# Sheet2.net
KiCad netlist of a schematic drawn in Altium Designer
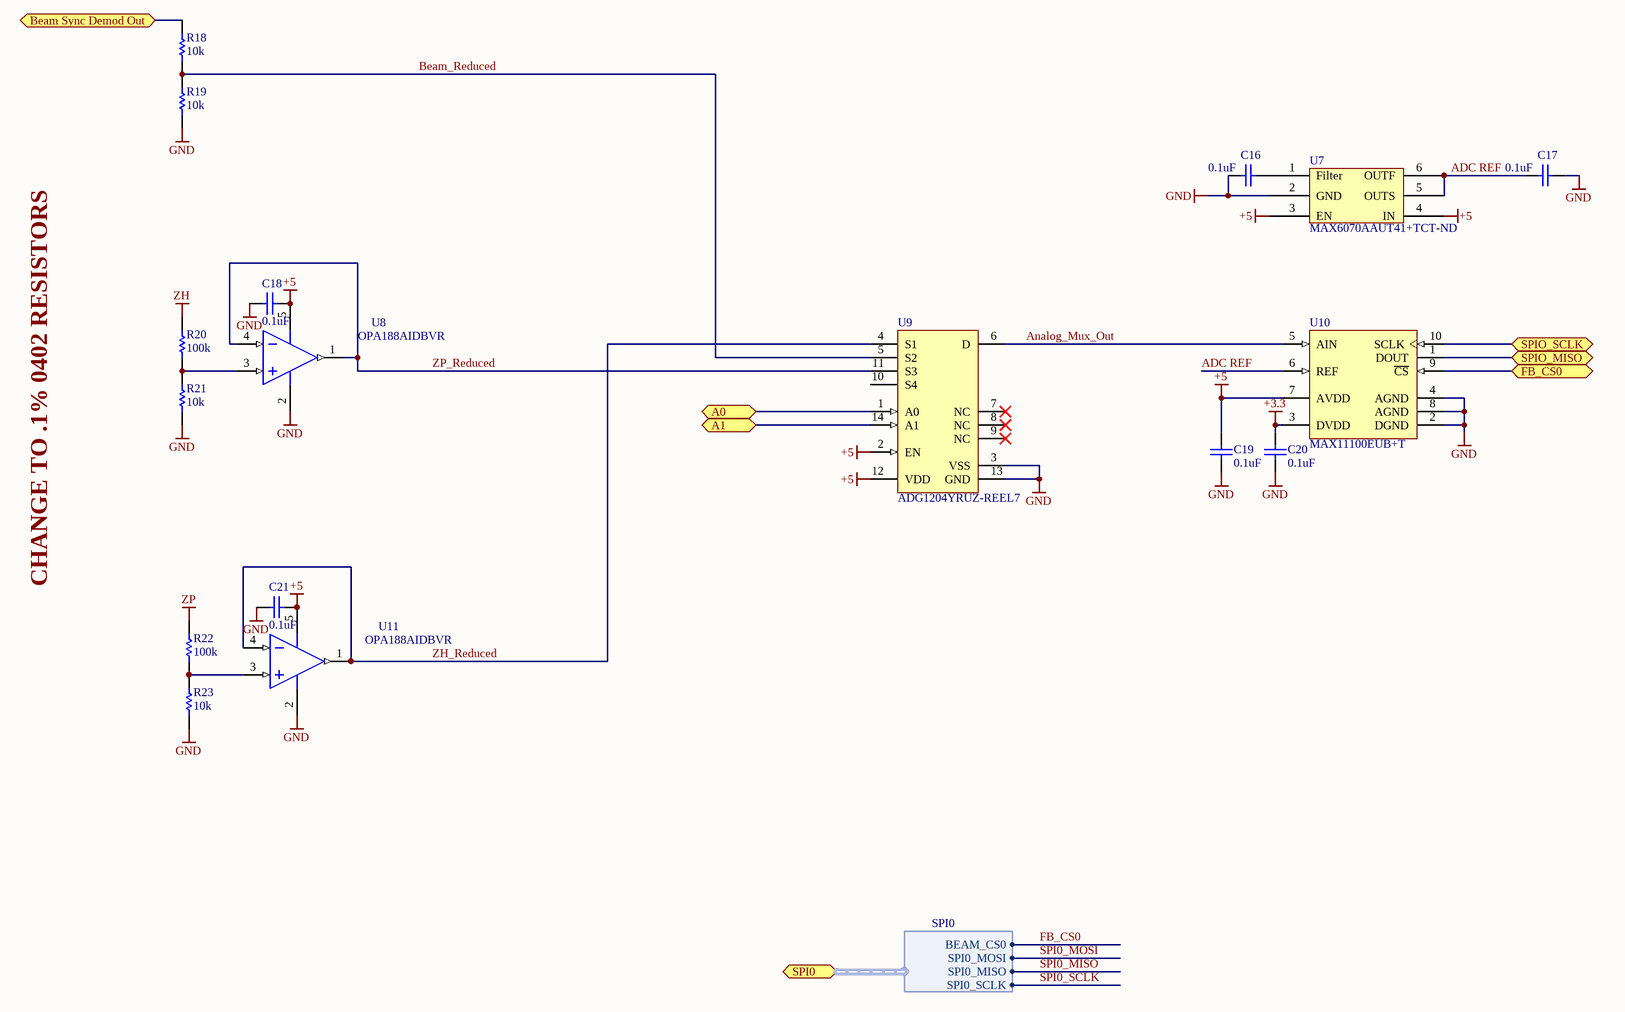
[diagram p0: Sheet2.SchDoc]

(export (version "E")
  (design (tool "Eeschema 10.0.6"))
  (components
    (comp (ref "C16")
      (value "0.1uF")
      (footprint "CAPC0402(1005)60_L")
      (description "CAP CER 0.1UF 10V X7R 0402")
      (fields
        (field (name "MANUFACTURER") "Murata Electronics North America")
        (field (name "MANUFACTURER PART NUMBER") "GRM155R71A104KA01D")
      )
      (libsource (lib "Altium Content Vault") (part "CMP-1034-00252-1"))
    )
    (comp (ref "C17")
      (value "0.1uF")
      (footprint "CAPC0402(1005)60_L")
      (description "CAP CER 0.1UF 10V X7R 0402")
      (fields
        (field (name "MANUFACTURER") "Murata Electronics North America")
        (field (name "MANUFACTURER PART NUMBER") "GRM155R71A104KA01D")
      )
      (libsource (lib "Altium Content Vault") (part "CMP-1034-00252-1"))
    )
    (comp (ref "C18")
      (value "0.1uF")
      (footprint "CAPC0402(1005)60_L")
      (description "CAP CER 0.1UF 10V X7R 0402")
      (fields
        (field (name "MANUFACTURER") "Murata Electronics North America")
        (field (name "MANUFACTURER PART NUMBER") "GRM155R71A104KA01D")
      )
      (libsource (lib "Altium Content Vault") (part "CMP-1034-00252-1"))
    )
    (comp (ref "C19")
      (value "0.1uF")
      (footprint "CAPC0402(1005)60_L")
      (description "CAP CER 0.1UF 10V X7R 0402")
      (fields
        (field (name "MANUFACTURER") "Murata Electronics North America")
        (field (name "MANUFACTURER PART NUMBER") "GRM155R71A104KA01D")
      )
      (libsource (lib "Altium Content Vault") (part "CMP-1034-00252-1"))
    )
    (comp (ref "C20")
      (value "0.1uF")
      (footprint "CAPC0402(1005)60_L")
      (description "CAP CER 0.1UF 10V X7R 0402")
      (fields
        (field (name "MANUFACTURER") "Murata Electronics North America")
        (field (name "MANUFACTURER PART NUMBER") "GRM155R71A104KA01D")
      )
      (libsource (lib "Altium Content Vault") (part "CMP-1034-00252-1"))
    )
    (comp (ref "C21")
      (value "0.1uF")
      (footprint "CAPC0402(1005)60_L")
      (description "CAP CER 0.1UF 10V X7R 0402")
      (fields
        (field (name "MANUFACTURER") "Murata Electronics North America")
        (field (name "MANUFACTURER PART NUMBER") "GRM155R71A104KA01D")
      )
      (libsource (lib "Altium Content Vault") (part "CMP-1034-00252-1"))
    )
    (comp (ref "R18")
      (value "10k")
      (footprint "RESC0402(1005)_M")
      (description "RES SMD 10K OHM 1% 1/8W 0402")
      (fields
        (field (name "MANUFACTURER") "Vishay Dale")
        (field (name "MANUFACTURER PART NUMBER") "CRCW0402100KFKEDHP")
      )
      (libsource (lib "Altium Content Vault") (part "CMP-1011-00651-1"))
    )
    (comp (ref "R19")
      (value "10k")
      (footprint "RESC0402(1005)_M")
      (description "RES SMD 10K OHM 1% 1/8W 0402")
      (fields
        (field (name "MANUFACTURER") "Vishay Dale")
        (field (name "MANUFACTURER PART NUMBER") "CRCW0402100KFKEDHP")
      )
      (libsource (lib "Altium Content Vault") (part "CMP-1011-00651-1"))
    )
    (comp (ref "R20")
      (value "100k")
      (footprint "RESC0402(1005)_M")
      (description "RES SMD 100K OHM 1% 1/8W 0402")
      (fields
        (field (name "MANUFACTURER") "Vishay Dale")
        (field (name "MANUFACTURER PART NUMBER") "CRCW0402100KFKEDHP")
      )
      (libsource (lib "Altium Content Vault") (part "CMP-1011-00651-1"))
    )
    (comp (ref "R21")
      (value "10k")
      (footprint "RESC0402(1005)_M")
      (description "RES SMD 10K OHM 1% 1/8W 0402")
      (fields
        (field (name "MANUFACTURER") "Vishay Dale")
        (field (name "MANUFACTURER PART NUMBER") "CRCW0402100KFKEDHP")
      )
      (libsource (lib "Altium Content Vault") (part "CMP-1011-00651-1"))
    )
    (comp (ref "R22")
      (value "100k")
      (footprint "RESC0402(1005)_M")
      (description "RES SMD 100K OHM 1% 1/8W 0402")
      (fields
        (field (name "MANUFACTURER") "Vishay Dale")
        (field (name "MANUFACTURER PART NUMBER") "CRCW0402100KFKEDHP")
      )
      (libsource (lib "Altium Content Vault") (part "CMP-1011-00651-1"))
    )
    (comp (ref "R23")
      (value "10k")
      (footprint "RESC0402(1005)_M")
      (description "RES SMD 10K OHM 1% 1/8W 0402")
      (fields
        (field (name "MANUFACTURER") "Vishay Dale")
        (field (name "MANUFACTURER PART NUMBER") "CRCW0402100KFKEDHP")
      )
      (libsource (lib "Altium Content Vault") (part "CMP-1011-00651-1"))
    )
    (comp (ref "U7")
      (value "MAX6070AAUT41+T")
      (footprint "SOT95P280X445-6N")
      (description "IC VREF SERIES 4.096V SOT23")
      (fields
        (field (name "SUPPLIER PART NUMBER 1") "MAX6070AAUT41+TCT-ND")
        (field (name "MANUFACTURER") "Maxim Integrated")
        (field (name "TOLERANCE") "±0.04%")
      )
      (libsource (lib "ZLS_Schematic_lib") (part "MAX6070AAUT41+T"))
    )
    (comp (ref "U8")
      (value "OPA188AIDBVR")
      (footprint "DBV0005A_M")
      (fields (field (name "MANUFACTURER") "Texas Instruments"))
      (libsource (lib "Altium Content Vault") (part "CMP-0809-00005-2"))
    )
    (comp (ref "U9")
      (value "ADG1204YRUZ-REEL7")
      (footprint "ADI-RU-14_L")
      (fields (field (name "MANUFACTURER") "Analog Devices"))
      (libsource (lib "Altium Content Vault") (part "ADI-ADG1204-RU-14"))
    )
    (comp (ref "U10")
      (value "MAX11100EUB+T")
      (footprint "U10+2_L")
      (description "16-Bit, +5V, 200ksps ADC with 10uA Shutdown, 10-Pin uMAX, -40°C to +85°C, Pb-Free, Tape and Reel")
      (libsource (lib "Altium Content Vault") (part "CON-ADC-MAX11100-IL10"))
    )
    (comp (ref "U11")
      (value "OPA188AIDBVR")
      (footprint "DBV0005A_M")
      (fields (field (name "MANUFACTURER") "Texas Instruments"))
      (libsource (lib "Altium Content Vault") (part "CMP-0809-00005-2"))
    )
  )
  (nets
    (net (code "2") (name "+3.3") (class "Default")
      (node (ref "C20") (pin "1") (pinfunction "1_1") (pintype "passive"))
      (node (ref "U10") (pin "3") (pinfunction "DVDD_3") (pintype "power_in"))
    )
    (net (code "3") (name "+5") (class "Default")
      (node (ref "C18") (pin "2") (pinfunction "2_2") (pintype "passive"))
      (node (ref "C19") (pin "1") (pinfunction "1_1") (pintype "passive"))
      (node (ref "C21") (pin "2") (pinfunction "2_2") (pintype "passive"))
      (node (ref "U10") (pin "7") (pinfunction "AVDD_7") (pintype "power_in"))
      (node (ref "U11") (pin "5") (pinfunction "V+_5") (pintype "power_in"))
      (node (ref "U7") (pin "3") (pinfunction "EN_3") (pintype "passive"))
      (node (ref "U7") (pin "4") (pinfunction "IN_4") (pintype "passive"))
      (node (ref "U8") (pin "5") (pinfunction "V+_5") (pintype "power_in"))
      (node (ref "U9") (pin "12") (pinfunction "VDD_12") (pintype "power_in"))
      (node (ref "U9") (pin "2") (pinfunction "EN_2") (pintype "input"))
    )
    (net (code "4") (name "/A0") (class "Default")
      (node (ref "U9") (pin "1") (pinfunction "A0_1") (pintype "input"))
    )
    (net (code "5") (name "/A1") (class "Default")
      (node (ref "U9") (pin "14") (pinfunction "A1_14") (pintype "input"))
    )
    (net (code "6") (name "/ADC REF") (class "Default")
      (node (ref "C17") (pin "2") (pinfunction "2_2") (pintype "passive"))
      (node (ref "U10") (pin "6") (pinfunction "REF_6") (pintype "input"))
      (node (ref "U7") (pin "5") (pinfunction "OUTS_5") (pintype "passive"))
      (node (ref "U7") (pin "6") (pinfunction "OUTF_6") (pintype "passive"))
    )
    (net (code "7") (name "/Analog_Mux_Out") (class "Default")
      (node (ref "U10") (pin "5") (pinfunction "AIN_5") (pintype "input"))
      (node (ref "U9") (pin "6") (pinfunction "D_6") (pintype "passive"))
    )
    (net (code "8") (name "/Beam Sync Demod Out") (class "Default")
      (node (ref "R18") (pin "2") (pinfunction "2_2") (pintype "passive"))
    )
    (net (code "9") (name "/Beam_Reduced") (class "Default")
      (node (ref "R18") (pin "1") (pinfunction "1_1") (pintype "passive"))
      (node (ref "R19") (pin "2") (pinfunction "2_2") (pintype "passive"))
      (node (ref "U9") (pin "5") (pinfunction "S2_5") (pintype "passive"))
    )
    (net (code "10") (name "/FB_CS0") (class "Default")
      (node (ref "U10") (pin "9") (pinfunction "~{CS}_9") (pintype "input"))
    )
    (net (code "14") (name "/SPIO_MISO") (class "Default")
      (node (ref "U10") (pin "1") (pinfunction "DOUT_1") (pintype "tri_state"))
    )
    (net (code "15") (name "/SPIO_SCLK") (class "Default")
      (node (ref "U10") (pin "10") (pinfunction "SCLK_10") (pintype "input"))
    )
    (net (code "16") (name "/ZH_Reduced") (class "Default")
      (node (ref "U11") (pin "1") (pinfunction "OUT_1") (pintype "output"))
      (node (ref "U11") (pin "4") (pinfunction "IN-_4") (pintype "input"))
      (node (ref "U9") (pin "4") (pinfunction "S1_4") (pintype "passive"))
    )
    (net (code "17") (name "/ZP_Reduced") (class "Default")
      (node (ref "U8") (pin "1") (pinfunction "OUT_1") (pintype "output"))
      (node (ref "U8") (pin "4") (pinfunction "IN-_4") (pintype "input"))
      (node (ref "U9") (pin "11") (pinfunction "S3_11") (pintype "passive"))
    )
    (net (code "19") (name "GND") (class "Default")
      (node (ref "C16") (pin "2") (pinfunction "2_2") (pintype "passive"))
      (node (ref "C17") (pin "1") (pinfunction "1_1") (pintype "passive"))
      (node (ref "C18") (pin "1") (pinfunction "1_1") (pintype "passive"))
      (node (ref "C19") (pin "2") (pinfunction "2_2") (pintype "passive"))
      (node (ref "C20") (pin "2") (pinfunction "2_2") (pintype "passive"))
      (node (ref "C21") (pin "1") (pinfunction "1_1") (pintype "passive"))
      (node (ref "R19") (pin "1") (pinfunction "1_1") (pintype "passive"))
      (node (ref "R21") (pin "1") (pinfunction "1_1") (pintype "passive"))
      (node (ref "R23") (pin "1") (pinfunction "1_1") (pintype "passive"))
      (node (ref "U10") (pin "2") (pinfunction "DGND_2") (pintype "power_in"))
      (node (ref "U10") (pin "4") (pinfunction "AGND_4") (pintype "power_in"))
      (node (ref "U10") (pin "8") (pinfunction "AGND_8") (pintype "power_in"))
      (node (ref "U11") (pin "2") (pinfunction "V-_2") (pintype "power_in"))
      (node (ref "U7") (pin "2") (pinfunction "GND_2") (pintype "passive"))
      (node (ref "U8") (pin "2") (pinfunction "V-_2") (pintype "power_in"))
      (node (ref "U9") (pin "13") (pinfunction "GND_13") (pintype "power_in"))
      (node (ref "U9") (pin "3") (pinfunction "VSS_3") (pintype "power_in"))
    )
    (net (code "20") (name "Net-(U7-Filter)") (class "Default")
      (node (ref "C16") (pin "1") (pinfunction "1_1") (pintype "passive"))
      (node (ref "U7") (pin "1") (pinfunction "Filter_1") (pintype "passive"))
    )
    (net (code "21") (name "Net-(U8-IN+)") (class "Default")
      (node (ref "R20") (pin "1") (pinfunction "1_1") (pintype "passive"))
      (node (ref "R21") (pin "2") (pinfunction "2_2") (pintype "passive"))
      (node (ref "U8") (pin "3") (pinfunction "IN+_3") (pintype "input"))
    )
    (net (code "22") (name "Net-(U11-IN+)") (class "Default")
      (node (ref "R22") (pin "1") (pinfunction "1_1") (pintype "passive"))
      (node (ref "R23") (pin "2") (pinfunction "2_2") (pintype "passive"))
      (node (ref "U11") (pin "3") (pinfunction "IN+_3") (pintype "input"))
    )
    (net (code "23") (name "ZH") (class "Default")
      (node (ref "R20") (pin "2") (pinfunction "2_2") (pintype "passive"))
    )
    (net (code "24") (name "ZP") (class "Default")
      (node (ref "R22") (pin "2") (pinfunction "2_2") (pintype "passive"))
    )
    (net (code "25") (name "unconnected-(U9-NC-Pad7)") (class "Default")
      (node (ref "U9") (pin "7") (pinfunction "NC_7") (pintype "passive+no_connect"))
    )
    (net (code "26") (name "unconnected-(U9-NC-Pad8)") (class "Default")
      (node (ref "U9") (pin "8") (pinfunction "NC_8") (pintype "passive+no_connect"))
    )
    (net (code "27") (name "unconnected-(U9-NC-Pad9)") (class "Default")
      (node (ref "U9") (pin "9") (pinfunction "NC_9") (pintype "passive+no_connect"))
    )
    (net (code "28") (name "unconnected-(U9-S4-Pad10)") (class "Default")
      (node (ref "U9") (pin "10") (pinfunction "S4_10") (pintype "passive"))
    )
  )
)
